# PWR_SMPS.net
KiCad netlist of a schematic drawn in Altium Designer
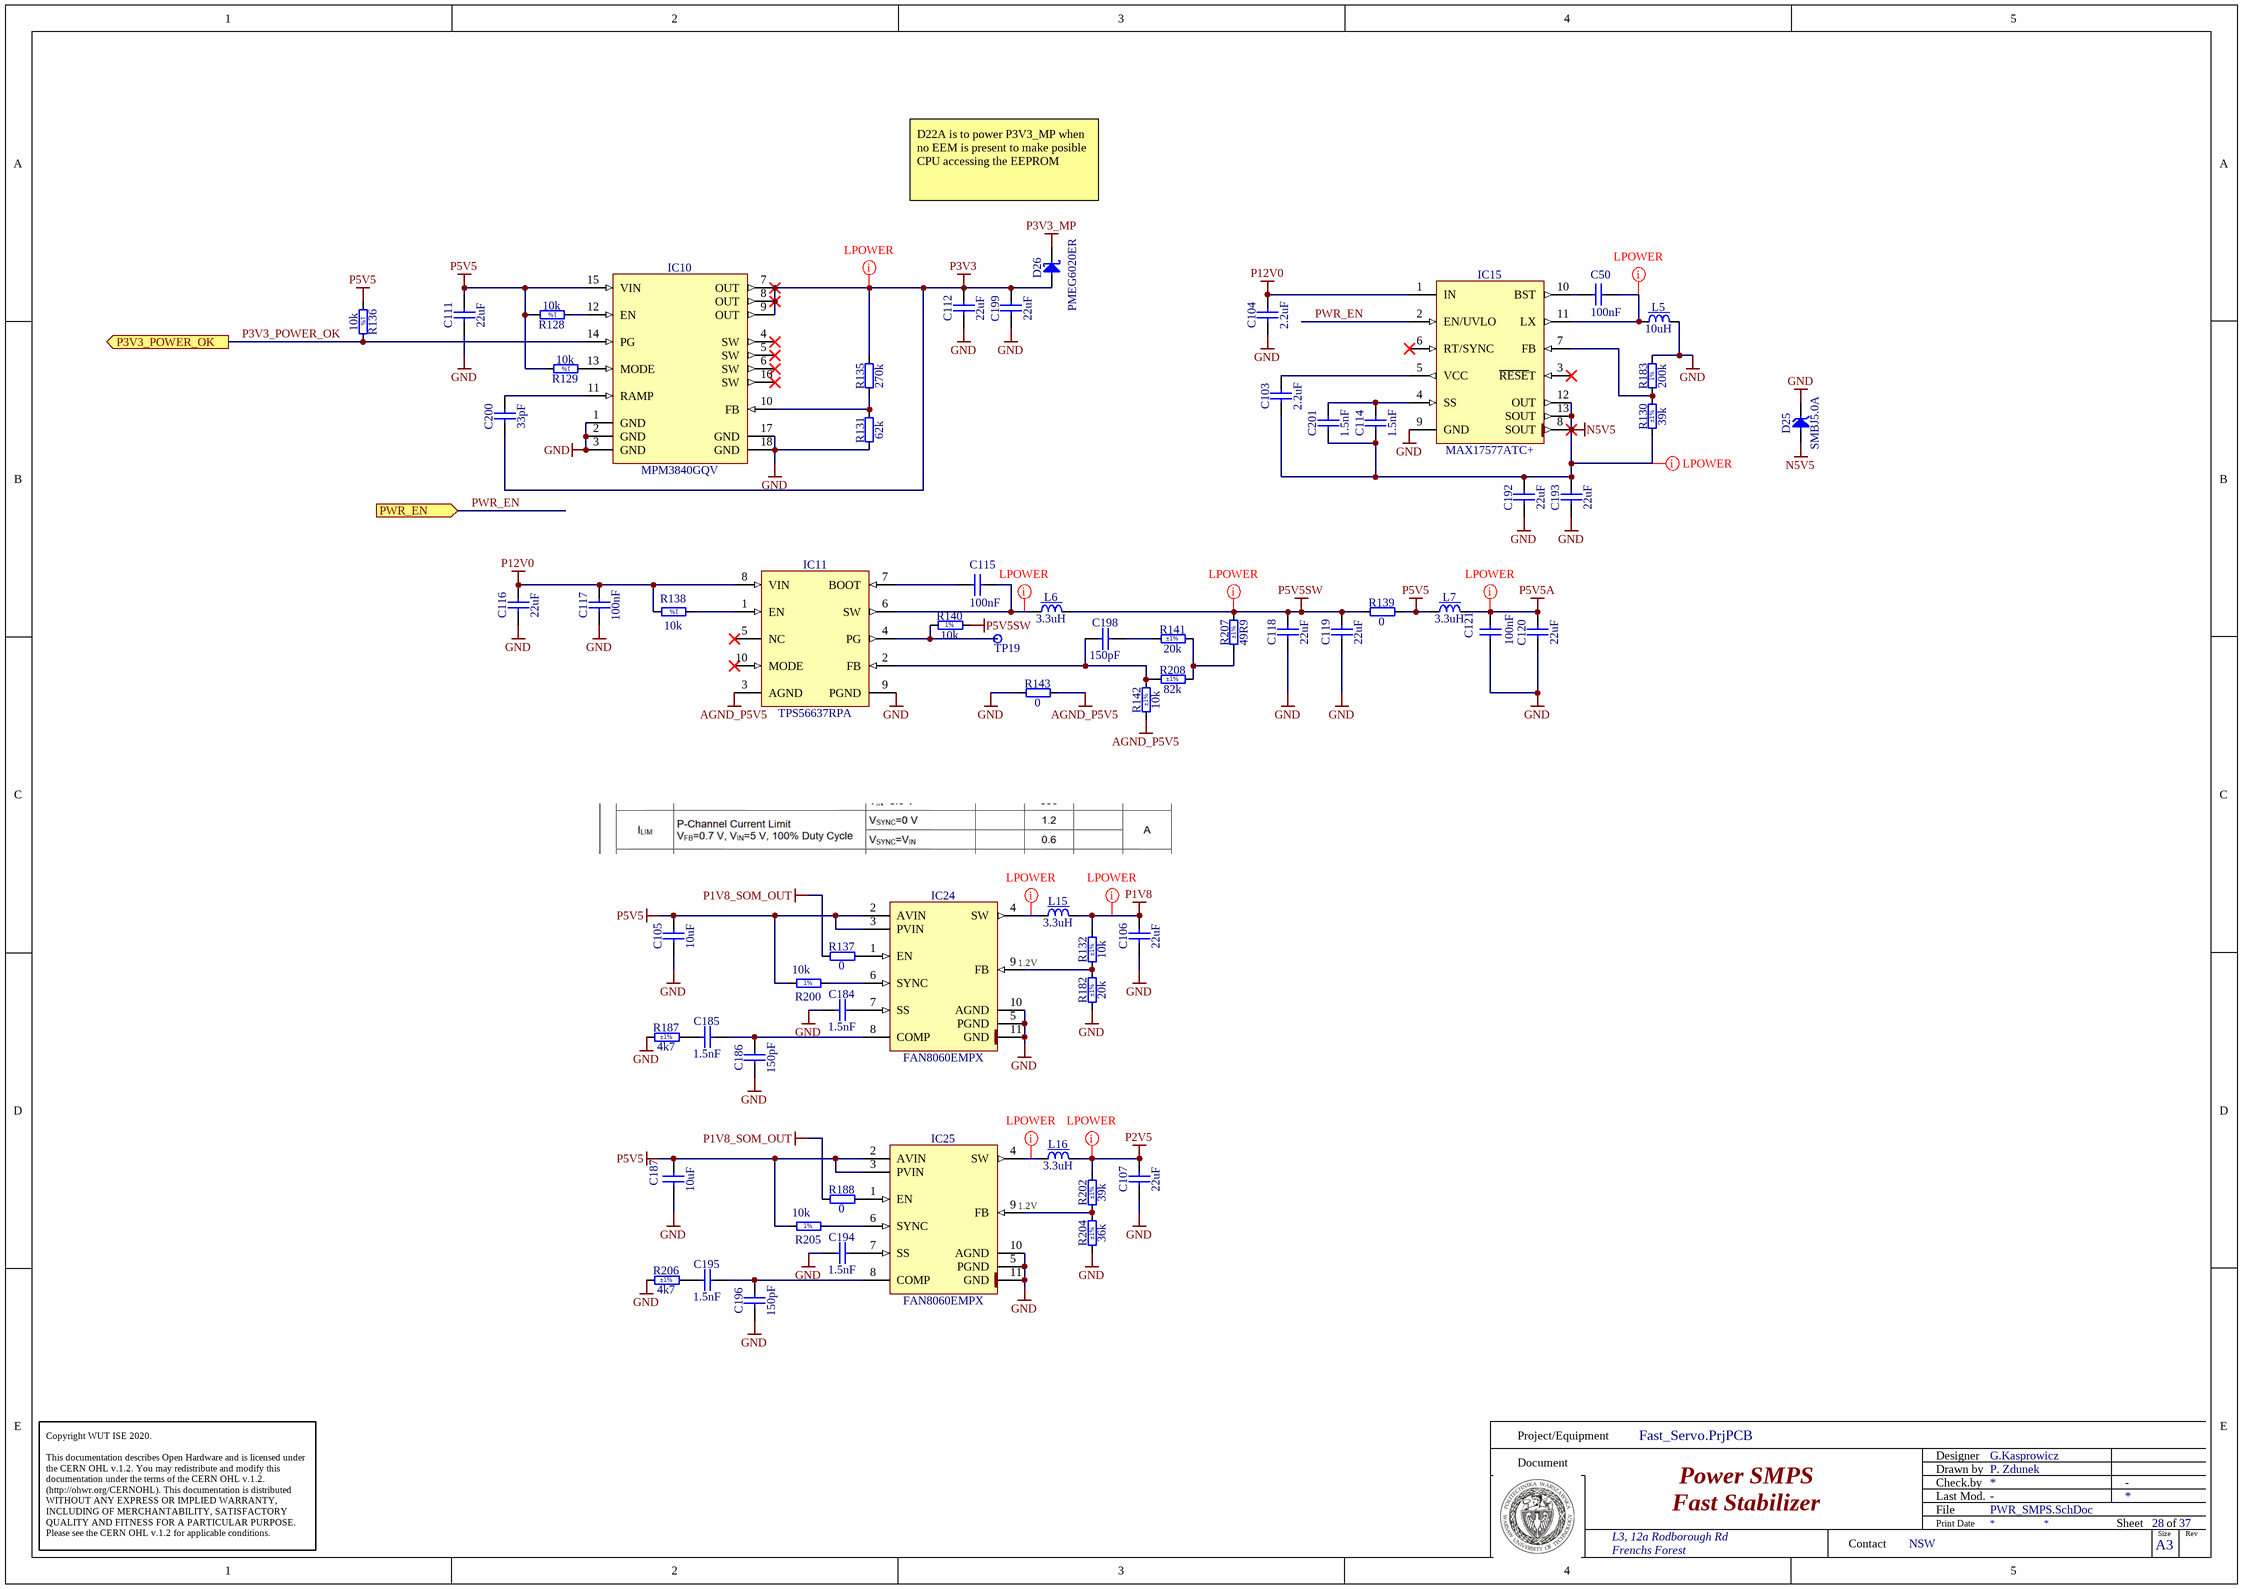
[diagram p0: PWR_SMPS.SchDoc]

(export (version "E")
  (design (tool "Eeschema 10.0.6"))
  (components
    (comp (ref "C50")
      (value "100nF")
      (footprint "CAPC1005X55N")
      (description "Non-polarised capacitor")
      (fields
        (field (name "PART NUMBER") "CC0402_100NF_16V_10%_X5R")
        (field (name "VOLTAGE") "16V")
        (field (name "AUTHOR") "CERN DEM JLC")
      )
      (libsource (lib "Capacitors") (part "Capacitor - non polarized"))
    )
    (comp (ref "C103")
      (value "2.2uF")
      (footprint "CAPC2012X140N")
      (description "Non-polarised capacitor")
      (fields
        (field (name "PART NUMBER") "CC0805_2.2UF_50V_10%_X7R")
        (field (name "VOLTAGE") "50V")
        (field (name "AUTHOR") "CERN DEM JLC")
      )
      (libsource (lib "Capacitors") (part "Capacitor - non polarized"))
    )
    (comp (ref "C104")
      (value "2.2uF")
      (footprint "CAPC2012X140N")
      (description "Non-polarised capacitor")
      (fields
        (field (name "PART NUMBER") "CC0805_2.2UF_50V_10%_X7R")
        (field (name "VOLTAGE") "50V")
        (field (name "AUTHOR") "CERN DEM JLC")
      )
      (libsource (lib "Capacitors") (part "Capacitor - non polarized"))
    )
    (comp (ref "C105")
      (value "10uF")
      (footprint "CAPC1608X80N")
      (description "Non-polarised capacitor")
      (fields
        (field (name "PART NUMBER") "CC0603_10UF_10V_10%_X5R")
        (field (name "VOLTAGE") "10V")
        (field (name "AUTHOR") "CERN DEM JLC")
      )
      (libsource (lib "Capacitors") (part "Capacitor - non polarized"))
    )
    (comp (ref "C106")
      (value "22uF")
      (footprint "CAPC2012X135N")
      (description "Non-polarised capacitor")
      (fields
        (field (name "PART NUMBER") "CC0805_22UF_16V_10%_X5R")
        (field (name "VOLTAGE") "16V")
        (field (name "AUTHOR") "CERN DEM JLC")
      )
      (libsource (lib "Capacitors") (part "Capacitor - non polarized"))
    )
    (comp (ref "C107")
      (value "22uF")
      (footprint "CAPC2012X135N")
      (description "Non-polarised capacitor")
      (fields
        (field (name "PART NUMBER") "CC0805_22UF_16V_10%_X5R")
        (field (name "VOLTAGE") "16V")
        (field (name "AUTHOR") "CERN DEM JLC")
      )
      (libsource (lib "Capacitors") (part "Capacitor - non polarized"))
    )
    (comp (ref "C111")
      (value "22uF")
      (footprint "CAPC2012X135N")
      (description "Non-polarised capacitor")
      (fields
        (field (name "PART NUMBER") "CC0805_22UF_16V_10%_X5R")
        (field (name "VOLTAGE") "16V")
        (field (name "AUTHOR") "CERN DEM JLC")
      )
      (libsource (lib "Capacitors") (part "Capacitor - non polarized"))
    )
    (comp (ref "C112")
      (value "22uF")
      (footprint "CAPC2012X135N")
      (description "Non-polarised capacitor")
      (fields
        (field (name "PART NUMBER") "CC0805_22UF_16V_10%_X5R")
        (field (name "VOLTAGE") "16V")
        (field (name "AUTHOR") "CERN DEM JLC")
      )
      (libsource (lib "Capacitors") (part "Capacitor - non polarized"))
    )
    (comp (ref "C114")
      (value "1.5nF")
      (footprint "CAPC1005X55N")
      (description "Non-polarised capacitor")
      (fields
        (field (name "PART NUMBER") "CC0402_1.5NF_50V_5%_C0G")
        (field (name "VOLTAGE") "50V")
        (field (name "AUTHOR") "CERN DEM BC")
      )
      (libsource (lib "Capacitors") (part "Capacitor - non polarized"))
    )
    (comp (ref "C115")
      (value "100nF")
      (footprint "CAPC1005X55N")
      (description "Non-polarised capacitor")
      (fields
        (field (name "PART NUMBER") "CC0402_100NF_16V_10%_X5R")
        (field (name "VOLTAGE") "16V")
        (field (name "AUTHOR") "CERN DEM JLC")
      )
      (libsource (lib "Capacitors") (part "Capacitor - non polarized"))
    )
    (comp (ref "C116")
      (value "22uF")
      (footprint "CAPC2012X135N")
      (description "Non-polarised capacitor")
      (fields
        (field (name "PART NUMBER") "CC0805_22UF_16V_10%_X5R")
        (field (name "VOLTAGE") "16V")
        (field (name "AUTHOR") "CERN DEM JLC")
      )
      (libsource (lib "Capacitors") (part "Capacitor - non polarized"))
    )
    (comp (ref "C117")
      (value "100nF")
      (footprint "CAPC1005X55N")
      (description "Non-polarised capacitor")
      (fields
        (field (name "PART NUMBER") "CC0402_100NF_16V_10%_X5R")
        (field (name "VOLTAGE") "16V")
        (field (name "AUTHOR") "CERN DEM JLC")
      )
      (libsource (lib "Capacitors") (part "Capacitor - non polarized"))
    )
    (comp (ref "C118")
      (value "22uF")
      (footprint "CAPC2012X135N")
      (description "Non-polarised capacitor")
      (fields
        (field (name "PART NUMBER") "CC0805_22UF_16V_10%_X5R")
        (field (name "VOLTAGE") "16V")
        (field (name "AUTHOR") "CERN DEM JLC")
      )
      (libsource (lib "Capacitors") (part "Capacitor - non polarized"))
    )
    (comp (ref "C119")
      (value "22uF")
      (footprint "CAPC2012X135N")
      (description "Non-polarised capacitor")
      (fields
        (field (name "PART NUMBER") "CC0805_22UF_16V_10%_X5R")
        (field (name "VOLTAGE") "16V")
        (field (name "AUTHOR") "CERN DEM JLC")
      )
      (libsource (lib "Capacitors") (part "Capacitor - non polarized"))
    )
    (comp (ref "C120")
      (value "22uF")
      (footprint "CAPC2012X135N")
      (description "Non-polarised capacitor")
      (fields
        (field (name "PART NUMBER") "CC0805_22UF_16V_10%_X5R")
        (field (name "VOLTAGE") "16V")
        (field (name "AUTHOR") "CERN DEM JLC")
      )
      (libsource (lib "Capacitors") (part "Capacitor - non polarized"))
    )
    (comp (ref "C121")
      (value "100nF")
      (footprint "CAPC1005X55N")
      (description "Non-polarised capacitor")
      (fields
        (field (name "PART NUMBER") "CC0402_100NF_16V_10%_X5R")
        (field (name "VOLTAGE") "16V")
        (field (name "AUTHOR") "CERN DEM JLC")
      )
      (libsource (lib "Capacitors") (part "Capacitor - non polarized"))
    )
    (comp (ref "C184")
      (value "1.5nF")
      (footprint "CAPC1005X55N")
      (description "Non-polarised capacitor")
      (fields
        (field (name "PART NUMBER") "CC0402_1.5NF_50V_5%_C0G")
        (field (name "VOLTAGE") "50V")
        (field (name "AUTHOR") "CERN DEM BC")
      )
      (libsource (lib "Capacitors") (part "Capacitor - non polarized"))
    )
    (comp (ref "C185")
      (value "1.5nF")
      (footprint "CAPC1005X55N")
      (description "Non-polarised capacitor")
      (fields
        (field (name "PART NUMBER") "CC0402_1.5NF_50V_5%_C0G")
        (field (name "VOLTAGE") "50V")
        (field (name "AUTHOR") "CERN DEM BC")
      )
      (libsource (lib "Capacitors") (part "Capacitor - non polarized"))
    )
    (comp (ref "C186")
      (value "150pF")
      (footprint "CAPC1005X55N")
      (description "Non-polarised capacitor")
      (fields
        (field (name "PART NUMBER") "CC0402_150PF_50V_5%_C0G")
        (field (name "VOLTAGE") "50V")
        (field (name "AUTHOR") "CERN DEM JLC")
      )
      (libsource (lib "Capacitors") (part "Capacitor - non polarized"))
    )
    (comp (ref "C187")
      (value "10uF")
      (footprint "CAPC1608X80N")
      (description "Non-polarised capacitor")
      (fields
        (field (name "PART NUMBER") "CC0603_10UF_10V_10%_X5R")
        (field (name "VOLTAGE") "10V")
        (field (name "AUTHOR") "CERN DEM JLC")
      )
      (libsource (lib "Capacitors") (part "Capacitor - non polarized"))
    )
    (comp (ref "C192")
      (value "22uF")
      (footprint "CAPC2012X135N")
      (description "Non-polarised capacitor")
      (fields
        (field (name "PART NUMBER") "CC0805_22UF_16V_10%_X5R")
        (field (name "VOLTAGE") "16V")
        (field (name "AUTHOR") "CERN DEM JLC")
      )
      (libsource (lib "Capacitors") (part "Capacitor - non polarized"))
    )
    (comp (ref "C193")
      (value "22uF")
      (footprint "CAPC2012X135N")
      (description "Non-polarised capacitor")
      (fields
        (field (name "PART NUMBER") "CC0805_22UF_16V_10%_X5R")
        (field (name "VOLTAGE") "16V")
        (field (name "AUTHOR") "CERN DEM JLC")
      )
      (libsource (lib "Capacitors") (part "Capacitor - non polarized"))
    )
    (comp (ref "C194")
      (value "1.5nF")
      (footprint "CAPC1005X55N")
      (description "Non-polarised capacitor")
      (fields
        (field (name "PART NUMBER") "CC0402_1.5NF_50V_5%_C0G")
        (field (name "VOLTAGE") "50V")
        (field (name "AUTHOR") "CERN DEM BC")
      )
      (libsource (lib "Capacitors") (part "Capacitor - non polarized"))
    )
    (comp (ref "C195")
      (value "1.5nF")
      (footprint "CAPC1005X55N")
      (description "Non-polarised capacitor")
      (fields
        (field (name "PART NUMBER") "CC0402_1.5NF_50V_5%_C0G")
        (field (name "VOLTAGE") "50V")
        (field (name "AUTHOR") "CERN DEM BC")
      )
      (libsource (lib "Capacitors") (part "Capacitor - non polarized"))
    )
    (comp (ref "C196")
      (value "150pF")
      (footprint "CAPC1005X55N")
      (description "Non-polarised capacitor")
      (fields
        (field (name "PART NUMBER") "CC0402_150PF_50V_5%_C0G")
        (field (name "VOLTAGE") "50V")
        (field (name "AUTHOR") "CERN DEM JLC")
      )
      (libsource (lib "Capacitors") (part "Capacitor - non polarized"))
    )
    (comp (ref "C198")
      (value "150pF")
      (footprint "CAPC1005X55N")
      (description "Non-polarised capacitor")
      (fields
        (field (name "PART NUMBER") "CC0402_150PF_50V_5%_C0G")
        (field (name "VOLTAGE") "50V")
        (field (name "AUTHOR") "CERN DEM JLC")
      )
      (libsource (lib "Capacitors") (part "Capacitor - non polarized"))
    )
    (comp (ref "C199")
      (value "22uF")
      (footprint "CAPC2012X135N")
      (description "Non-polarised capacitor")
      (fields
        (field (name "PART NUMBER") "CC0805_22UF_16V_10%_X5R")
        (field (name "VOLTAGE") "16V")
        (field (name "AUTHOR") "CERN DEM JLC")
      )
      (libsource (lib "Capacitors") (part "Capacitor - non polarized"))
    )
    (comp (ref "C200")
      (value "33pF")
      (footprint "CAPC1608X87N")
      (description "Non-polarised capacitor")
      (fields
        (field (name "PART NUMBER") "CC0603_33PF_50V_5%_NP0")
        (field (name "VOLTAGE") "50V")
        (field (name "AUTHOR") "CERN DEM JLC")
      )
      (libsource (lib "Capacitors") (part "Capacitor - non polarized"))
    )
    (comp (ref "C201")
      (value "1.5nF")
      (footprint "CAPC1005X55N")
      (description "Non-polarised capacitor")
      (fields
        (field (name "PART NUMBER") "CC0402_1.5NF_50V_5%_C0G")
        (field (name "VOLTAGE") "50V")
        (field (name "AUTHOR") "CERN DEM BC")
      )
      (libsource (lib "Capacitors") (part "Capacitor - non polarized"))
    )
    (comp (ref "D25")
      (value "SMBJ5.0A")
      (footprint "DIOM5336X265N")
      (description "Zener Diode")
      (fields (field (name "VOLTAGE") "5V") (field (name "POWER") "600W") (field (name "AUTHOR") "GK"))
      (libsource (lib "ICs And Semiconductors") (part "Diode Zener"))
    )
    (comp (ref "D26")
      (value "PMEG6020ER")
      (footprint "SODFL3517X110N")
      (description "Schottky Diode")
      (fields
        (field (name "VOLTAGE") "60V")
        (field (name "POWER") "2A")
        (field (name "AUTHOR") "CERN DEM JMW")
      )
      (libsource (lib "ICs And Semiconductors") (part "Diode Schottky"))
    )
    (comp (ref "IC10")
      (value "MPM3840GQV")
      (footprint "MPS_MPM38XXGQV")
      (description "2.8V to 5.5V Input, 4A, Power Module Synchronous Step-Down Converter with Integrated Inductor")
      (fields
        (field (name "MANUFACTURER") "MPS (MONOLITIC  POWER SYSTEMS)")
        (field (name "AUTHOR") "CERN DEM BC")
      )
      (libsource (lib "ICs And Semiconductors") (part "MPM3840GQV"))
    )
    (comp (ref "IC11")
      (value "TPS56637RPA")
      (footprint "TEXAS_RPA0010A")
      (description "4.5V to 28V Input, 6A Synchronous Buck Converter")
      (fields (field (name "MANUFACTURER") "TEXAS INSTRUMENTS") (field (name "AUTHOR") "CERN DEM BC"))
      (libsource (lib "ICs And Semiconductors") (part "TPS56637RPA"))
    )
    (comp (ref "IC15")
      (value "MAX17577ATC+")
      (footprint "SON50P300X300X80-13N-R180X260")
      (description "4.5V to 60V, 1A High-Efficiency, Synchronous, Inverting Output DC-DC Converters")
      (fields (field (name "MANUFACTURER") "MAXIM") (field (name "AUTHOR") "CERN DEM HF"))
      (libsource (lib "ICs And Semiconductors") (part "MAX17577"))
    )
    (comp (ref "IC24")
      (value "FAN8060EMPX")
      (footprint "SON50P300X80_HS-11N")
      (description "2.5 to 5.5 V 1 A 1.2 MHz Step-Down DC/DC")
      (fields (field (name "MANUFACTURER") "ON SEMICONDUCTOR") (field (name "AUTHOR") "GK"))
      (libsource (lib "Regulators_SMPS") (part "PM_FAN8060"))
    )
    (comp (ref "IC25")
      (value "FAN8060EMPX")
      (footprint "SON50P300X80_HS-11N")
      (description "2.5 to 5.5 V 1 A 1.2 MHz Step-Down DC/DC")
      (fields (field (name "MANUFACTURER") "ON SEMICONDUCTOR") (field (name "AUTHOR") "GK"))
      (libsource (lib "Regulators_SMPS") (part "PM_FAN8060"))
    )
    (comp (ref "L5")
      (value "10uH")
      (footprint "IND_TDK_VLCF5020-1")
      (description "Inductor With Core")
      (fields
        (field (name "PART NUMBER") "IND_10UH_20%_TDK_VLCF5020-1")
        (field (name "POWER") "1.5A")
        (field (name "AUTHOR") "CERN DEM JLC")
      )
      (libsource (lib "Inductors & Transformers") (part "Inductor With Magnetic core"))
    )
    (comp (ref "L6")
      (value "3.3uH")
      (footprint "INDM6965X300N")
      (description "Inductor With Core")
      (fields
        (field (name "PART NUMBER") "IND2525_3.3UH_20%_VISHAY_IHLP-2525CZ-01")
        (field (name "POWER") "6A")
        (field (name "AUTHOR") "CERN DEM MR")
      )
      (libsource (lib "Inductors & Transformers") (part "Inductor With Magnetic core"))
    )
    (comp (ref "L7")
      (value "3.3uH")
      (footprint "IND_WURTH_WE-TPC_4828")
      (description "Inductor With Core")
      (fields
        (field (name "PART NUMBER") "IND_3.3UH_30%_WURTH_WE-TPC_744043003")
        (field (name "POWER") "2.15A")
        (field (name "AUTHOR") "CERN DEM JLC")
      )
      (libsource (lib "Inductors & Transformers") (part "Inductor With Magnetic core"))
    )
    (comp (ref "L15")
      (value "3.3uH")
      (footprint "IND_WURTH_WE-TPC_4828")
      (description "Inductor With Core")
      (fields
        (field (name "PART NUMBER") "IND_3.3UH_30%_WURTH_WE-TPC_744043003")
        (field (name "POWER") "2.15A")
        (field (name "AUTHOR") "CERN DEM JLC")
      )
      (libsource (lib "Inductors & Transformers") (part "Inductor With Magnetic core"))
    )
    (comp (ref "L16")
      (value "3.3uH")
      (footprint "IND_WURTH_WE-TPC_4828")
      (description "Inductor With Core")
      (fields
        (field (name "PART NUMBER") "IND_3.3UH_30%_WURTH_WE-TPC_744043003")
        (field (name "POWER") "2.15A")
        (field (name "AUTHOR") "CERN DEM JLC")
      )
      (libsource (lib "Inductors & Transformers") (part "Inductor With Magnetic core"))
    )
    (comp (ref "R128")
      (value "10k")
      (footprint "RESC1005X40N")
      (description "Resistor - 1%")
      (fields
        (field (name "PART NUMBER") "R0402_10K_1%_0.0625W_100PPM")
        (field (name "MANUFACTURER") "GENERIC")
        (field (name "AUTHOR") "CERN DEM JLC")
      )
      (libsource (lib "Resistors") (part "Resistor - 1%"))
    )
    (comp (ref "R129")
      (value "10k")
      (footprint "RESC1005X40N")
      (description "Resistor - 1%")
      (fields
        (field (name "PART NUMBER") "R0402_10K_1%_0.0625W_100PPM")
        (field (name "MANUFACTURER") "GENERIC")
        (field (name "AUTHOR") "CERN DEM JLC")
      )
      (libsource (lib "Resistors") (part "Resistor - 1%"))
    )
    (comp (ref "R130")
      (value "39k")
      (footprint "RESC1005X40N")
      (description "Resistor - 1%")
      (fields
        (field (name "TOLERANCE") "±1%")
        (field (name "PART NUMBER") "R0402_39K_1%_0.0625W_100PPM")
        (field (name "POWER") "0.0625W")
        (field (name "AUTHOR") "CERN DEM JLC")
      )
      (libsource (lib "Resistors") (part "Resistor - 1%"))
    )
    (comp (ref "R131")
      (value "62k")
      (footprint "RESC1005X40N")
      (description "Resistor - 1%")
      (fields
        (field (name "PART NUMBER") "R0402_62K_1%_0.0625W_100PPM")
        (field (name "MANUFACTURER") "GENERIC")
        (field (name "AUTHOR") "CERN DEM JLC")
      )
      (libsource (lib "Resistors") (part "Resistor - 1%"))
    )
    (comp (ref "R132")
      (value "10k")
      (footprint "RESC1005X40N")
      (description "Resistor - 1%")
      (fields
        (field (name "TOLERANCE") "±1%")
        (field (name "PART NUMBER") "R0402_10K_1%_0.0625W_100PPM")
        (field (name "POWER") "0.0625W")
        (field (name "AUTHOR") "CERN DEM JLC")
      )
      (libsource (lib "Resistors") (part "Resistor - 1%"))
    )
    (comp (ref "R135")
      (value "270k")
      (footprint "RESC1005X40N")
      (description "Resistor - 1%")
      (fields
        (field (name "PART NUMBER") "R0402_270K_1%_0.0625W_100PPM")
        (field (name "MANUFACTURER") "GENERIC")
        (field (name "AUTHOR") "CERN DEM JLC")
      )
      (libsource (lib "Resistors") (part "Resistor - 1%"))
    )
    (comp (ref "R136")
      (value "10k")
      (footprint "RESC1005X40N")
      (description "Resistor - 1%")
      (fields
        (field (name "PART NUMBER") "R0402_10K_1%_0.0625W_100PPM")
        (field (name "MANUFACTURER") "GENERIC")
        (field (name "AUTHOR") "CERN DEM JLC")
      )
      (libsource (lib "Resistors") (part "Resistor - 1%"))
    )
    (comp (ref "R137")
      (value "0")
      (footprint "RESC1005X40N")
      (description "Resistor")
      (fields
        (field (name "PART NUMBER") "R0402_0R_JUMPER")
        (field (name "MANUFACTURER") "GENERIC")
        (field (name "AUTHOR") "CERN DEM JLC")
      )
      (libsource (lib "Resistors") (part "Resistor"))
    )
    (comp (ref "R138")
      (value "10k")
      (footprint "RESC1005X40N")
      (description "Resistor - 1%")
      (fields
        (field (name "PART NUMBER") "R0402_10K_1%_0.0625W_100PPM")
        (field (name "MANUFACTURER") "GENERIC")
        (field (name "AUTHOR") "CERN DEM JLC")
      )
      (libsource (lib "Resistors") (part "Resistor - 1%"))
    )
    (comp (ref "R139")
      (value "0")
      (footprint "RESC3116X80N")
      (description "Resistor")
      (fields
        (field (name "PART NUMBER") "R1206_0R_JUMPER_SEI_HCJ")
        (field (name "MANUFACTURER") "SEI (STACKPOLE ELECTRONICS INC.)")
        (field (name "AUTHOR") "CERN DEM MR")
      )
      (libsource (lib "Resistors") (part "Resistor"))
    )
    (comp (ref "R140")
      (value "10k")
      (footprint "RESC1005X40N")
      (description "Resistor - 1%")
      (fields
        (field (name "PART NUMBER") "R0402_10K_1%_0.0625W_100PPM")
        (field (name "MANUFACTURER") "GENERIC")
        (field (name "AUTHOR") "CERN DEM JLC")
      )
      (libsource (lib "Resistors") (part "Resistor - 1%"))
    )
    (comp (ref "R141")
      (value "20k")
      (footprint "RESC1005X40N")
      (description "Resistor - 1%")
      (fields
        (field (name "TOLERANCE") "±1%")
        (field (name "PART NUMBER") "R0402_20K_1%_0.0625W_100PPM")
        (field (name "POWER") "0.0625W")
        (field (name "AUTHOR") "CERN DEM JLC")
      )
      (libsource (lib "Resistors") (part "Resistor - 1%"))
    )
    (comp (ref "R142")
      (value "10k")
      (footprint "RESC1005X40N")
      (description "Resistor - 1%")
      (fields
        (field (name "TOLERANCE") "±1%")
        (field (name "PART NUMBER") "R0402_10K_1%_0.0625W_100PPM")
        (field (name "POWER") "0.0625W")
        (field (name "AUTHOR") "CERN DEM JLC")
      )
      (libsource (lib "Resistors") (part "Resistor - 1%"))
    )
    (comp (ref "R143")
      (value "0")
      (footprint "RESC1005X40N")
      (description "Resistor")
      (fields
        (field (name "PART NUMBER") "R0402_0R_JUMPER")
        (field (name "MANUFACTURER") "GENERIC")
        (field (name "AUTHOR") "CERN DEM JLC")
      )
      (libsource (lib "Resistors") (part "Resistor"))
    )
    (comp (ref "R182")
      (value "20k")
      (footprint "RESC1005X40N")
      (description "Resistor - 1%")
      (fields
        (field (name "TOLERANCE") "±1%")
        (field (name "PART NUMBER") "R0402_20K_1%_0.0625W_100PPM")
        (field (name "POWER") "0.0625W")
        (field (name "AUTHOR") "CERN DEM JLC")
      )
      (libsource (lib "Resistors") (part "Resistor - 1%"))
    )
    (comp (ref "R183")
      (value "200k")
      (footprint "RESC1005X40N")
      (description "Resistor - 1%")
      (fields
        (field (name "PART NUMBER") "R0402_200K_1%_0.0625W_100PPM")
        (field (name "POWER") "0.0625W")
        (field (name "AUTHOR") "CERN DEM JLC")
      )
      (libsource (lib "Resistors") (part "Resistor - 1%"))
    )
    (comp (ref "R187")
      (value "4k7")
      (footprint "RESC1005X40N")
      (description "Resistor - 1%")
      (fields
        (field (name "TOLERANCE") "±1%")
        (field (name "PART NUMBER") "R0402_4K7_1%_0.0625W_100PPM")
        (field (name "POWER") "0.0625W")
        (field (name "AUTHOR") "CERN DEM JLC")
      )
      (libsource (lib "Resistors") (part "Resistor - 1%"))
    )
    (comp (ref "R188")
      (value "0")
      (footprint "RESC1005X40N")
      (description "Resistor")
      (fields
        (field (name "PART NUMBER") "R0402_0R_JUMPER")
        (field (name "MANUFACTURER") "GENERIC")
        (field (name "AUTHOR") "CERN DEM JLC")
      )
      (libsource (lib "Resistors") (part "Resistor"))
    )
    (comp (ref "R200")
      (value "10k")
      (footprint "RESC1005X40N")
      (description "Resistor - 1%")
      (fields
        (field (name "PART NUMBER") "R0402_10K_1%_0.0625W_100PPM")
        (field (name "MANUFACTURER") "GENERIC")
        (field (name "AUTHOR") "CERN DEM JLC")
      )
      (libsource (lib "Resistors") (part "Resistor - 1%"))
    )
    (comp (ref "R202")
      (value "39k")
      (footprint "RESC1005X40N")
      (description "Resistor - 1%")
      (fields
        (field (name "TOLERANCE") "±1%")
        (field (name "PART NUMBER") "R0402_39K_1%_0.0625W_100PPM")
        (field (name "POWER") "0.0625W")
        (field (name "AUTHOR") "CERN DEM JLC")
      )
      (libsource (lib "Resistors") (part "Resistor - 1%"))
    )
    (comp (ref "R204")
      (value "36k")
      (footprint "RESC1005X40N")
      (description "Resistor - 1%")
      (fields
        (field (name "TOLERANCE") "±1%")
        (field (name "PART NUMBER") "R0402_36K_1%_0.0625W_100PPM")
        (field (name "POWER") "0.0625W")
        (field (name "AUTHOR") "CERN DEM JLC")
      )
      (libsource (lib "Resistors") (part "Resistor - 1%"))
    )
    (comp (ref "R205")
      (value "10k")
      (footprint "RESC1005X40N")
      (description "Resistor - 1%")
      (fields
        (field (name "PART NUMBER") "R0402_10K_1%_0.0625W_100PPM")
        (field (name "MANUFACTURER") "GENERIC")
        (field (name "AUTHOR") "CERN DEM JLC")
      )
      (libsource (lib "Resistors") (part "Resistor - 1%"))
    )
    (comp (ref "R206")
      (value "4k7")
      (footprint "RESC1005X40N")
      (description "Resistor - 1%")
      (fields
        (field (name "TOLERANCE") "±1%")
        (field (name "PART NUMBER") "R0402_4K7_1%_0.0625W_100PPM")
        (field (name "POWER") "0.0625W")
        (field (name "AUTHOR") "CERN DEM JLC")
      )
      (libsource (lib "Resistors") (part "Resistor - 1%"))
    )
    (comp (ref "R207")
      (value "49R9")
      (footprint "RESC1005X40N")
      (description "Resistor - 1%")
      (fields
        (field (name "TOLERANCE") "±1%")
        (field (name "PART NUMBER") "R0402_49R9_1%_0.0625W_100PPM")
        (field (name "POWER") "0.0625W")
        (field (name "AUTHOR") "CERN DEM JLC")
      )
      (libsource (lib "Resistors") (part "Resistor - 1%"))
    )
    (comp (ref "R208")
      (value "82k")
      (footprint "RESC1608X55N")
      (description "Resistor - 1%")
      (fields
        (field (name "TOLERANCE") "±1%")
        (field (name "PART NUMBER") "R0603_82K_1%_0.1W_100PPM")
        (field (name "POWER") "0.1W")
        (field (name "AUTHOR") "CERN DEM JLC")
      )
      (libsource (lib "") (part "Resistor - 1%_1"))
    )
    (comp (ref "TP19")
      (value "Test Point")
      (footprint "TPS127")
      (fields (field (name "PART NUMBER") "SMD_PAD_1.27X1.27MM") (field (name "AUTHOR") "CERN DEM JLC"))
      (libsource (lib "Eletro-mechanical") (part "Test Point"))
    )
  )
  (nets
    (net (code "1") (name "/P3V3_POWER_OK") (class "Default")
      (node (ref "IC10") (pin "14") (pinfunction "PG_14") (pintype "input"))
      (node (ref "R136") (pin "2") (pinfunction "2_2") (pintype "passive"))
    )
    (net (code "2") (name "/PWR_EN") (class "Default")
      (node (ref "IC15") (pin "2") (pinfunction "EN/UVLO_2") (pintype "input"))
    )
    (net (code "3") (name "AGND_P5V5") (class "Default")
      (node (ref "IC11") (pin "3") (pinfunction "AGND_3") (pintype "power_in"))
      (node (ref "R142") (pin "1") (pinfunction "1_1") (pintype "passive"))
      (node (ref "R143") (pin "2") (pinfunction "2_2") (pintype "passive"))
    )
    (net (code "4") (name "GND") (class "Default")
      (node (ref "C104") (pin "1") (pinfunction "1_1") (pintype "passive"))
      (node (ref "C105") (pin "1") (pinfunction "1_1") (pintype "passive"))
      (node (ref "C106") (pin "1") (pinfunction "1_1") (pintype "passive"))
      (node (ref "C107") (pin "1") (pinfunction "1_1") (pintype "passive"))
      (node (ref "C111") (pin "1") (pinfunction "1_1") (pintype "passive"))
      (node (ref "C112") (pin "1") (pinfunction "1_1") (pintype "passive"))
      (node (ref "C116") (pin "1") (pinfunction "1_1") (pintype "passive"))
      (node (ref "C117") (pin "1") (pinfunction "1_1") (pintype "passive"))
      (node (ref "C118") (pin "1") (pinfunction "1_1") (pintype "passive"))
      (node (ref "C119") (pin "1") (pinfunction "1_1") (pintype "passive"))
      (node (ref "C120") (pin "1") (pinfunction "1_1") (pintype "passive"))
      (node (ref "C121") (pin "1") (pinfunction "1_1") (pintype "passive"))
      (node (ref "C184") (pin "1") (pinfunction "1_1") (pintype "passive"))
      (node (ref "C186") (pin "1") (pinfunction "1_1") (pintype "passive"))
      (node (ref "C187") (pin "1") (pinfunction "1_1") (pintype "passive"))
      (node (ref "C192") (pin "1") (pinfunction "1_1") (pintype "passive"))
      (node (ref "C193") (pin "1") (pinfunction "1_1") (pintype "passive"))
      (node (ref "C194") (pin "1") (pinfunction "1_1") (pintype "passive"))
      (node (ref "C196") (pin "1") (pinfunction "1_1") (pintype "passive"))
      (node (ref "C199") (pin "1") (pinfunction "1_1") (pintype "passive"))
      (node (ref "D25") (pin "1") (pinfunction "C_1") (pintype "passive"))
      (node (ref "IC10") (pin "1") (pinfunction "GND_1") (pintype "power_in"))
      (node (ref "IC10") (pin "17") (pinfunction "GND_17") (pintype "power_in"))
      (node (ref "IC10") (pin "18") (pinfunction "GND_18") (pintype "power_in"))
      (node (ref "IC10") (pin "2") (pinfunction "GND_2") (pintype "power_in"))
      (node (ref "IC10") (pin "3") (pinfunction "GND_3") (pintype "power_in"))
      (node (ref "IC11") (pin "9") (pinfunction "PGND_9") (pintype "power_in"))
      (node (ref "IC15") (pin "9") (pinfunction "GND_9") (pintype "power_in"))
      (node (ref "IC24") (pin "10") (pinfunction "AGND_10") (pintype "power_in"))
      (node (ref "IC24") (pin "11") (pinfunction "GND_11") (pintype "power_in"))
      (node (ref "IC24") (pin "5") (pinfunction "PGND_5") (pintype "power_in"))
      (node (ref "IC25") (pin "10") (pinfunction "AGND_10") (pintype "power_in"))
      (node (ref "IC25") (pin "11") (pinfunction "GND_11") (pintype "power_in"))
      (node (ref "IC25") (pin "5") (pinfunction "PGND_5") (pintype "power_in"))
      (node (ref "L5") (pin "2") (pinfunction "2_2") (pintype "passive"))
      (node (ref "R131") (pin "1") (pinfunction "1_1") (pintype "passive"))
      (node (ref "R143") (pin "1") (pinfunction "1_1") (pintype "passive"))
      (node (ref "R182") (pin "1") (pinfunction "1_1") (pintype "passive"))
      (node (ref "R183") (pin "2") (pinfunction "2_2") (pintype "passive"))
      (node (ref "R187") (pin "1") (pinfunction "1_1") (pintype "passive"))
      (node (ref "R204") (pin "1") (pinfunction "1_1") (pintype "passive"))
      (node (ref "R206") (pin "1") (pinfunction "1_1") (pintype "passive"))
    )
    (net (code "5") (name "N5V5") (class "Default")
      (node (ref "C103") (pin "1") (pinfunction "1_1") (pintype "passive"))
      (node (ref "C114") (pin "1") (pinfunction "1_1") (pintype "passive"))
      (node (ref "C192") (pin "2") (pinfunction "2_2") (pintype "passive"))
      (node (ref "C193") (pin "2") (pinfunction "2_2") (pintype "passive"))
      (node (ref "C201") (pin "1") (pinfunction "1_1") (pintype "passive"))
      (node (ref "D25") (pin "2") (pinfunction "A_2") (pintype "passive"))
      (node (ref "IC15") (pin "12") (pinfunction "OUT_12") (pintype "output"))
      (node (ref "IC15") (pin "13") (pinfunction "SOUT_13") (pintype "output"))
      (node (ref "IC15") (pin "8") (pinfunction "SOUT_8") (pintype "output"))
      (node (ref "R130") (pin "1") (pinfunction "1_1") (pintype "passive"))
    )
    (net (code "6") (name "Net-(C185-Pad1)") (class "Default")
      (node (ref "C185") (pin "1") (pinfunction "1_1") (pintype "passive"))
      (node (ref "R187") (pin "2") (pinfunction "2_2") (pintype "passive"))
    )
    (net (code "7") (name "Net-(C195-Pad1)") (class "Default")
      (node (ref "C195") (pin "1") (pinfunction "1_1") (pintype "passive"))
      (node (ref "R206") (pin "2") (pinfunction "2_2") (pintype "passive"))
    )
    (net (code "8") (name "Net-(C198-Pad2)") (class "Default")
      (node (ref "C198") (pin "2") (pinfunction "2_2") (pintype "passive"))
      (node (ref "R141") (pin "1") (pinfunction "1_1") (pintype "passive"))
    )
    (net (code "9") (name "Net-(IC10-EN)") (class "Default")
      (node (ref "IC10") (pin "12") (pinfunction "EN_12") (pintype "input"))
      (node (ref "R128") (pin "1") (pinfunction "1_1") (pintype "passive"))
    )
    (net (code "10") (name "Net-(IC10-FB)") (class "Default")
      (node (ref "IC10") (pin "10") (pinfunction "FB_10") (pintype "input"))
      (node (ref "R131") (pin "2") (pinfunction "2_2") (pintype "passive"))
      (node (ref "R135") (pin "1") (pinfunction "1_1") (pintype "passive"))
    )
    (net (code "11") (name "Net-(IC10-MODE)") (class "Default")
      (node (ref "IC10") (pin "13") (pinfunction "MODE_13") (pintype "input"))
      (node (ref "R129") (pin "1") (pinfunction "1_1") (pintype "passive"))
    )
    (net (code "12") (name "Net-(IC10-RAMP)") (class "Default")
      (node (ref "C200") (pin "2") (pinfunction "2_2") (pintype "passive"))
      (node (ref "IC10") (pin "11") (pinfunction "RAMP_11") (pintype "input"))
    )
    (net (code "13") (name "Net-(IC11-BOOT)") (class "Default")
      (node (ref "C115") (pin "2") (pinfunction "2_2") (pintype "passive"))
      (node (ref "IC11") (pin "7") (pinfunction "BOOT_7") (pintype "input"))
    )
    (net (code "14") (name "Net-(IC11-EN)") (class "Default")
      (node (ref "IC11") (pin "1") (pinfunction "EN_1") (pintype "input"))
      (node (ref "R138") (pin "1") (pinfunction "1_1") (pintype "passive"))
    )
    (net (code "15") (name "Net-(IC11-FB)") (class "Default")
      (node (ref "C198") (pin "1") (pinfunction "1_1") (pintype "passive"))
      (node (ref "IC11") (pin "2") (pinfunction "FB_2") (pintype "input"))
      (node (ref "R142") (pin "2") (pinfunction "2_2") (pintype "passive"))
      (node (ref "R208") (pin "1") (pinfunction "1_1") (pintype "passive"))
    )
    (net (code "16") (name "Net-(IC11-PG)") (class "Default")
      (node (ref "IC11") (pin "4") (pinfunction "PG_4") (pintype "output"))
      (node (ref "R140") (pin "1") (pinfunction "1_1") (pintype "passive"))
      (node (ref "TP19") (pin "1") (pinfunction "1_1") (pintype "bidirectional"))
    )
    (net (code "17") (name "Net-(IC11-SW)") (class "Default")
      (node (ref "C115") (pin "1") (pinfunction "1_1") (pintype "passive"))
      (node (ref "IC11") (pin "6") (pinfunction "SW_6") (pintype "output"))
      (node (ref "L6") (pin "1") (pinfunction "1_1") (pintype "passive"))
    )
    (net (code "18") (name "Net-(IC15-BST)") (class "Default")
      (node (ref "C50") (pin "2") (pinfunction "2_2") (pintype "passive"))
      (node (ref "IC15") (pin "10") (pinfunction "BST_10") (pintype "output"))
    )
    (net (code "19") (name "Net-(IC15-FB)") (class "Default")
      (node (ref "IC15") (pin "7") (pinfunction "FB_7") (pintype "input"))
      (node (ref "R130") (pin "2") (pinfunction "2_2") (pintype "passive"))
      (node (ref "R183") (pin "1") (pinfunction "1_1") (pintype "passive"))
    )
    (net (code "20") (name "Net-(IC15-LX)") (class "Default")
      (node (ref "C50") (pin "1") (pinfunction "1_1") (pintype "passive"))
      (node (ref "IC15") (pin "11") (pinfunction "LX_11") (pintype "output"))
      (node (ref "L5") (pin "1") (pinfunction "1_1") (pintype "passive"))
    )
    (net (code "21") (name "Net-(IC15-SS)") (class "Default")
      (node (ref "C114") (pin "2") (pinfunction "2_2") (pintype "passive"))
      (node (ref "C201") (pin "2") (pinfunction "2_2") (pintype "passive"))
      (node (ref "IC15") (pin "4") (pinfunction "SS_4") (pintype "input"))
    )
    (net (code "22") (name "Net-(IC15-VCC)") (class "Default")
      (node (ref "C103") (pin "2") (pinfunction "2_2") (pintype "passive"))
      (node (ref "IC15") (pin "5") (pinfunction "VCC_5") (pintype "output"))
    )
    (net (code "23") (name "Net-(IC24-COMP)") (class "Default")
      (node (ref "C185") (pin "2") (pinfunction "2_2") (pintype "passive"))
      (node (ref "C186") (pin "2") (pinfunction "2_2") (pintype "passive"))
      (node (ref "IC24") (pin "8") (pinfunction "COMP_8") (pintype "passive"))
    )
    (net (code "24") (name "Net-(IC24-EN)") (class "Default")
      (node (ref "IC24") (pin "1") (pinfunction "EN_1") (pintype "input"))
      (node (ref "R137") (pin "2") (pinfunction "2_2") (pintype "passive"))
    )
    (net (code "25") (name "Net-(IC24-FB)") (class "Default")
      (node (ref "IC24") (pin "9") (pinfunction "FB_9") (pintype "input"))
      (node (ref "R132") (pin "1") (pinfunction "1_1") (pintype "passive"))
      (node (ref "R182") (pin "2") (pinfunction "2_2") (pintype "passive"))
    )
    (net (code "26") (name "Net-(IC24-SS)") (class "Default")
      (node (ref "C184") (pin "2") (pinfunction "2_2") (pintype "passive"))
      (node (ref "IC24") (pin "7") (pinfunction "SS_7") (pintype "input"))
    )
    (net (code "27") (name "Net-(IC24-SW)") (class "Default")
      (node (ref "IC24") (pin "4") (pinfunction "SW_4") (pintype "output"))
      (node (ref "L15") (pin "1") (pinfunction "1_1") (pintype "passive"))
    )
    (net (code "28") (name "Net-(IC24-SYNC)") (class "Default")
      (node (ref "IC24") (pin "6") (pinfunction "SYNC_6") (pintype "input"))
      (node (ref "R200") (pin "2") (pinfunction "2_2") (pintype "passive"))
    )
    (net (code "29") (name "Net-(IC25-COMP)") (class "Default")
      (node (ref "C195") (pin "2") (pinfunction "2_2") (pintype "passive"))
      (node (ref "C196") (pin "2") (pinfunction "2_2") (pintype "passive"))
      (node (ref "IC25") (pin "8") (pinfunction "COMP_8") (pintype "passive"))
    )
    (net (code "30") (name "Net-(IC25-EN)") (class "Default")
      (node (ref "IC25") (pin "1") (pinfunction "EN_1") (pintype "input"))
      (node (ref "R188") (pin "2") (pinfunction "2_2") (pintype "passive"))
    )
    (net (code "31") (name "Net-(IC25-FB)") (class "Default")
      (node (ref "IC25") (pin "9") (pinfunction "FB_9") (pintype "input"))
      (node (ref "R202") (pin "1") (pinfunction "1_1") (pintype "passive"))
      (node (ref "R204") (pin "2") (pinfunction "2_2") (pintype "passive"))
    )
    (net (code "32") (name "Net-(IC25-SS)") (class "Default")
      (node (ref "C194") (pin "2") (pinfunction "2_2") (pintype "passive"))
      (node (ref "IC25") (pin "7") (pinfunction "SS_7") (pintype "input"))
    )
    (net (code "33") (name "Net-(IC25-SW)") (class "Default")
      (node (ref "IC25") (pin "4") (pinfunction "SW_4") (pintype "output"))
      (node (ref "L16") (pin "1") (pinfunction "1_1") (pintype "passive"))
    )
    (net (code "34") (name "Net-(IC25-SYNC)") (class "Default")
      (node (ref "IC25") (pin "6") (pinfunction "SYNC_6") (pintype "input"))
      (node (ref "R205") (pin "2") (pinfunction "2_2") (pintype "passive"))
    )
    (net (code "35") (name "Net-(R141-Pad2)") (class "Default")
      (node (ref "R141") (pin "2") (pinfunction "2_2") (pintype "passive"))
      (node (ref "R207") (pin "1") (pinfunction "1_1") (pintype "passive"))
      (node (ref "R208") (pin "2") (pinfunction "2_2") (pintype "passive"))
    )
    (net (code "36") (name "P1V8") (class "Default")
      (node (ref "C106") (pin "2") (pinfunction "2_2") (pintype "passive"))
      (node (ref "L15") (pin "2") (pinfunction "2_2") (pintype "passive"))
      (node (ref "R132") (pin "2") (pinfunction "2_2") (pintype "passive"))
    )
    (net (code "37") (name "P1V8_SOM_OUT") (class "Default")
      (node (ref "R137") (pin "1") (pinfunction "1_1") (pintype "passive"))
      (node (ref "R188") (pin "1") (pinfunction "1_1") (pintype "passive"))
    )
    (net (code "38") (name "P2V5") (class "Default")
      (node (ref "C107") (pin "2") (pinfunction "2_2") (pintype "passive"))
      (node (ref "L16") (pin "2") (pinfunction "2_2") (pintype "passive"))
      (node (ref "R202") (pin "2") (pinfunction "2_2") (pintype "passive"))
    )
    (net (code "39") (name "P3V3") (class "Default")
      (node (ref "C112") (pin "2") (pinfunction "2_2") (pintype "passive"))
      (node (ref "C199") (pin "2") (pinfunction "2_2") (pintype "passive"))
      (node (ref "C200") (pin "1") (pinfunction "1_1") (pintype "passive"))
      (node (ref "D26") (pin "2") (pinfunction "A_2") (pintype "passive"))
      (node (ref "IC10") (pin "7") (pinfunction "OUT_7") (pintype "output"))
      (node (ref "IC10") (pin "8") (pinfunction "OUT_8") (pintype "output"))
      (node (ref "IC10") (pin "9") (pinfunction "OUT_9") (pintype "output"))
      (node (ref "R135") (pin "2") (pinfunction "2_2") (pintype "passive"))
    )
    (net (code "40") (name "P3V3_MP") (class "Default")
      (node (ref "D26") (pin "1") (pinfunction "C_1") (pintype "passive"))
    )
    (net (code "41") (name "P5V5") (class "Default")
      (node (ref "C105") (pin "2") (pinfunction "2_2") (pintype "passive"))
      (node (ref "C111") (pin "2") (pinfunction "2_2") (pintype "passive"))
      (node (ref "C187") (pin "2") (pinfunction "2_2") (pintype "passive"))
      (node (ref "IC10") (pin "15") (pinfunction "VIN_15") (pintype "input"))
      (node (ref "IC24") (pin "2") (pinfunction "AVIN_2") (pintype "power_in"))
      (node (ref "IC24") (pin "3") (pinfunction "PVIN_3") (pintype "power_in"))
      (node (ref "IC25") (pin "2") (pinfunction "AVIN_2") (pintype "power_in"))
      (node (ref "IC25") (pin "3") (pinfunction "PVIN_3") (pintype "power_in"))
      (node (ref "L7") (pin "1") (pinfunction "1_1") (pintype "passive"))
      (node (ref "R128") (pin "2") (pinfunction "2_2") (pintype "passive"))
      (node (ref "R129") (pin "2") (pinfunction "2_2") (pintype "passive"))
      (node (ref "R136") (pin "1") (pinfunction "1_1") (pintype "passive"))
      (node (ref "R139") (pin "2") (pinfunction "2_2") (pintype "passive"))
      (node (ref "R200") (pin "1") (pinfunction "1_1") (pintype "passive"))
      (node (ref "R205") (pin "1") (pinfunction "1_1") (pintype "passive"))
    )
    (net (code "42") (name "P5V5A") (class "Default")
      (node (ref "C120") (pin "2") (pinfunction "2_2") (pintype "passive"))
      (node (ref "C121") (pin "2") (pinfunction "2_2") (pintype "passive"))
      (node (ref "L7") (pin "2") (pinfunction "2_2") (pintype "passive"))
    )
    (net (code "43") (name "P5V5SW") (class "Default")
      (node (ref "C118") (pin "2") (pinfunction "2_2") (pintype "passive"))
      (node (ref "C119") (pin "2") (pinfunction "2_2") (pintype "passive"))
      (node (ref "L6") (pin "2") (pinfunction "2_2") (pintype "passive"))
      (node (ref "R139") (pin "1") (pinfunction "1_1") (pintype "passive"))
      (node (ref "R140") (pin "2") (pinfunction "2_2") (pintype "passive"))
      (node (ref "R207") (pin "2") (pinfunction "2_2") (pintype "passive"))
    )
    (net (code "44") (name "P12V0") (class "Default")
      (node (ref "C104") (pin "2") (pinfunction "2_2") (pintype "passive"))
      (node (ref "C116") (pin "2") (pinfunction "2_2") (pintype "passive"))
      (node (ref "C117") (pin "2") (pinfunction "2_2") (pintype "passive"))
      (node (ref "IC11") (pin "8") (pinfunction "VIN_8") (pintype "input"))
      (node (ref "IC15") (pin "1") (pinfunction "IN_1") (pintype "power_in"))
      (node (ref "R138") (pin "2") (pinfunction "2_2") (pintype "passive"))
    )
    (net (code "45") (name "unconnected-(IC10-SW-Pad4)") (class "Default")
      (node (ref "IC10") (pin "4") (pinfunction "SW_4") (pintype "output+no_connect"))
    )
    (net (code "46") (name "unconnected-(IC10-SW-Pad5)") (class "Default")
      (node (ref "IC10") (pin "5") (pinfunction "SW_5") (pintype "output+no_connect"))
    )
    (net (code "47") (name "unconnected-(IC10-SW-Pad6)") (class "Default")
      (node (ref "IC10") (pin "6") (pinfunction "SW_6") (pintype "output+no_connect"))
    )
    (net (code "48") (name "unconnected-(IC10-SW-Pad16)") (class "Default")
      (node (ref "IC10") (pin "16") (pinfunction "SW_16") (pintype "output+no_connect"))
    )
    (net (code "49") (name "unconnected-(IC11-MODE-Pad10)") (class "Default")
      (node (ref "IC11") (pin "10") (pinfunction "MODE_10") (pintype "input+no_connect"))
    )
    (net (code "50") (name "unconnected-(IC11-NC-Pad5)") (class "Default")
      (node (ref "IC11") (pin "5") (pinfunction "NC_5") (pintype "passive+no_connect"))
    )
    (net (code "51") (name "unconnected-(IC15-RT{slash}SYNC-Pad6)") (class "Default")
      (node (ref "IC15") (pin "6") (pinfunction "RT/SYNC_6") (pintype "input+no_connect"))
    )
    (net (code "52") (name "unconnected-(IC15-~{RESE}T-Pad3)") (class "Default")
      (node (ref "IC15") (pin "3") (pinfunction "~{RESE}T_3") (pintype "input+no_connect"))
    )
  )
)
